# lcd33.net
KiCad netlist of a schematic drawn in Altium Designer
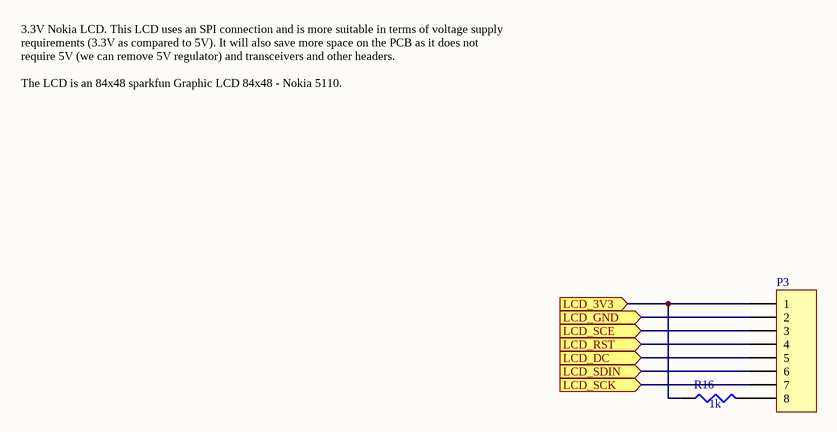
[diagram p0: lcd33.SchDoc]

(export (version "E")
  (design (tool "Eeschema 10.0.6"))
  (components
    (comp (ref "P3")
      (value "Header 8H")
      (footprint "HDR1X8H")
      (description "Header, 8-Pin, Right Angle")
      (libsource (lib "Miscellaneous Connectors") (part "Header 8H"))
    )
    (comp (ref "R16")
      (value "1k")
      (footprint "0603")
      (description "Resistor")
      (fields (field (name "Comment") "RES1"))
      (libsource (lib "RCLDQ") (part "RES1"))
    )
  )
  (nets
    (net (code "1") (name "/LCD_3V3") (class "Default")
      (node (ref "P3") (pin "1") (pinfunction "1_1") (pintype "passive"))
      (node (ref "R16") (pin "1") (pinfunction "1_1") (pintype "passive"))
    )
    (net (code "2") (name "/LCD_DC") (class "Default")
      (node (ref "P3") (pin "5") (pinfunction "5_5") (pintype "passive"))
    )
    (net (code "3") (name "/LCD_GND") (class "Default")
      (node (ref "P3") (pin "2") (pinfunction "2_2") (pintype "passive"))
    )
    (net (code "4") (name "/LCD_RST") (class "Default")
      (node (ref "P3") (pin "4") (pinfunction "4_4") (pintype "passive"))
    )
    (net (code "5") (name "/LCD_SCE") (class "Default")
      (node (ref "P3") (pin "3") (pinfunction "3_3") (pintype "passive"))
    )
    (net (code "6") (name "/LCD_SCK") (class "Default")
      (node (ref "P3") (pin "7") (pinfunction "7_7") (pintype "passive"))
    )
    (net (code "7") (name "/LCD_SDIN") (class "Default")
      (node (ref "P3") (pin "6") (pinfunction "6_6") (pintype "passive"))
    )
    (net (code "8") (name "Net-(P3-Pad8)") (class "Default")
      (node (ref "P3") (pin "8") (pinfunction "8_8") (pintype "passive"))
      (node (ref "R16") (pin "2") (pinfunction "2_2") (pintype "passive"))
    )
  )
)
